# NodeNadelAdapter_v1_2.net
KiCad netlist of a schematic drawn in EAGLE
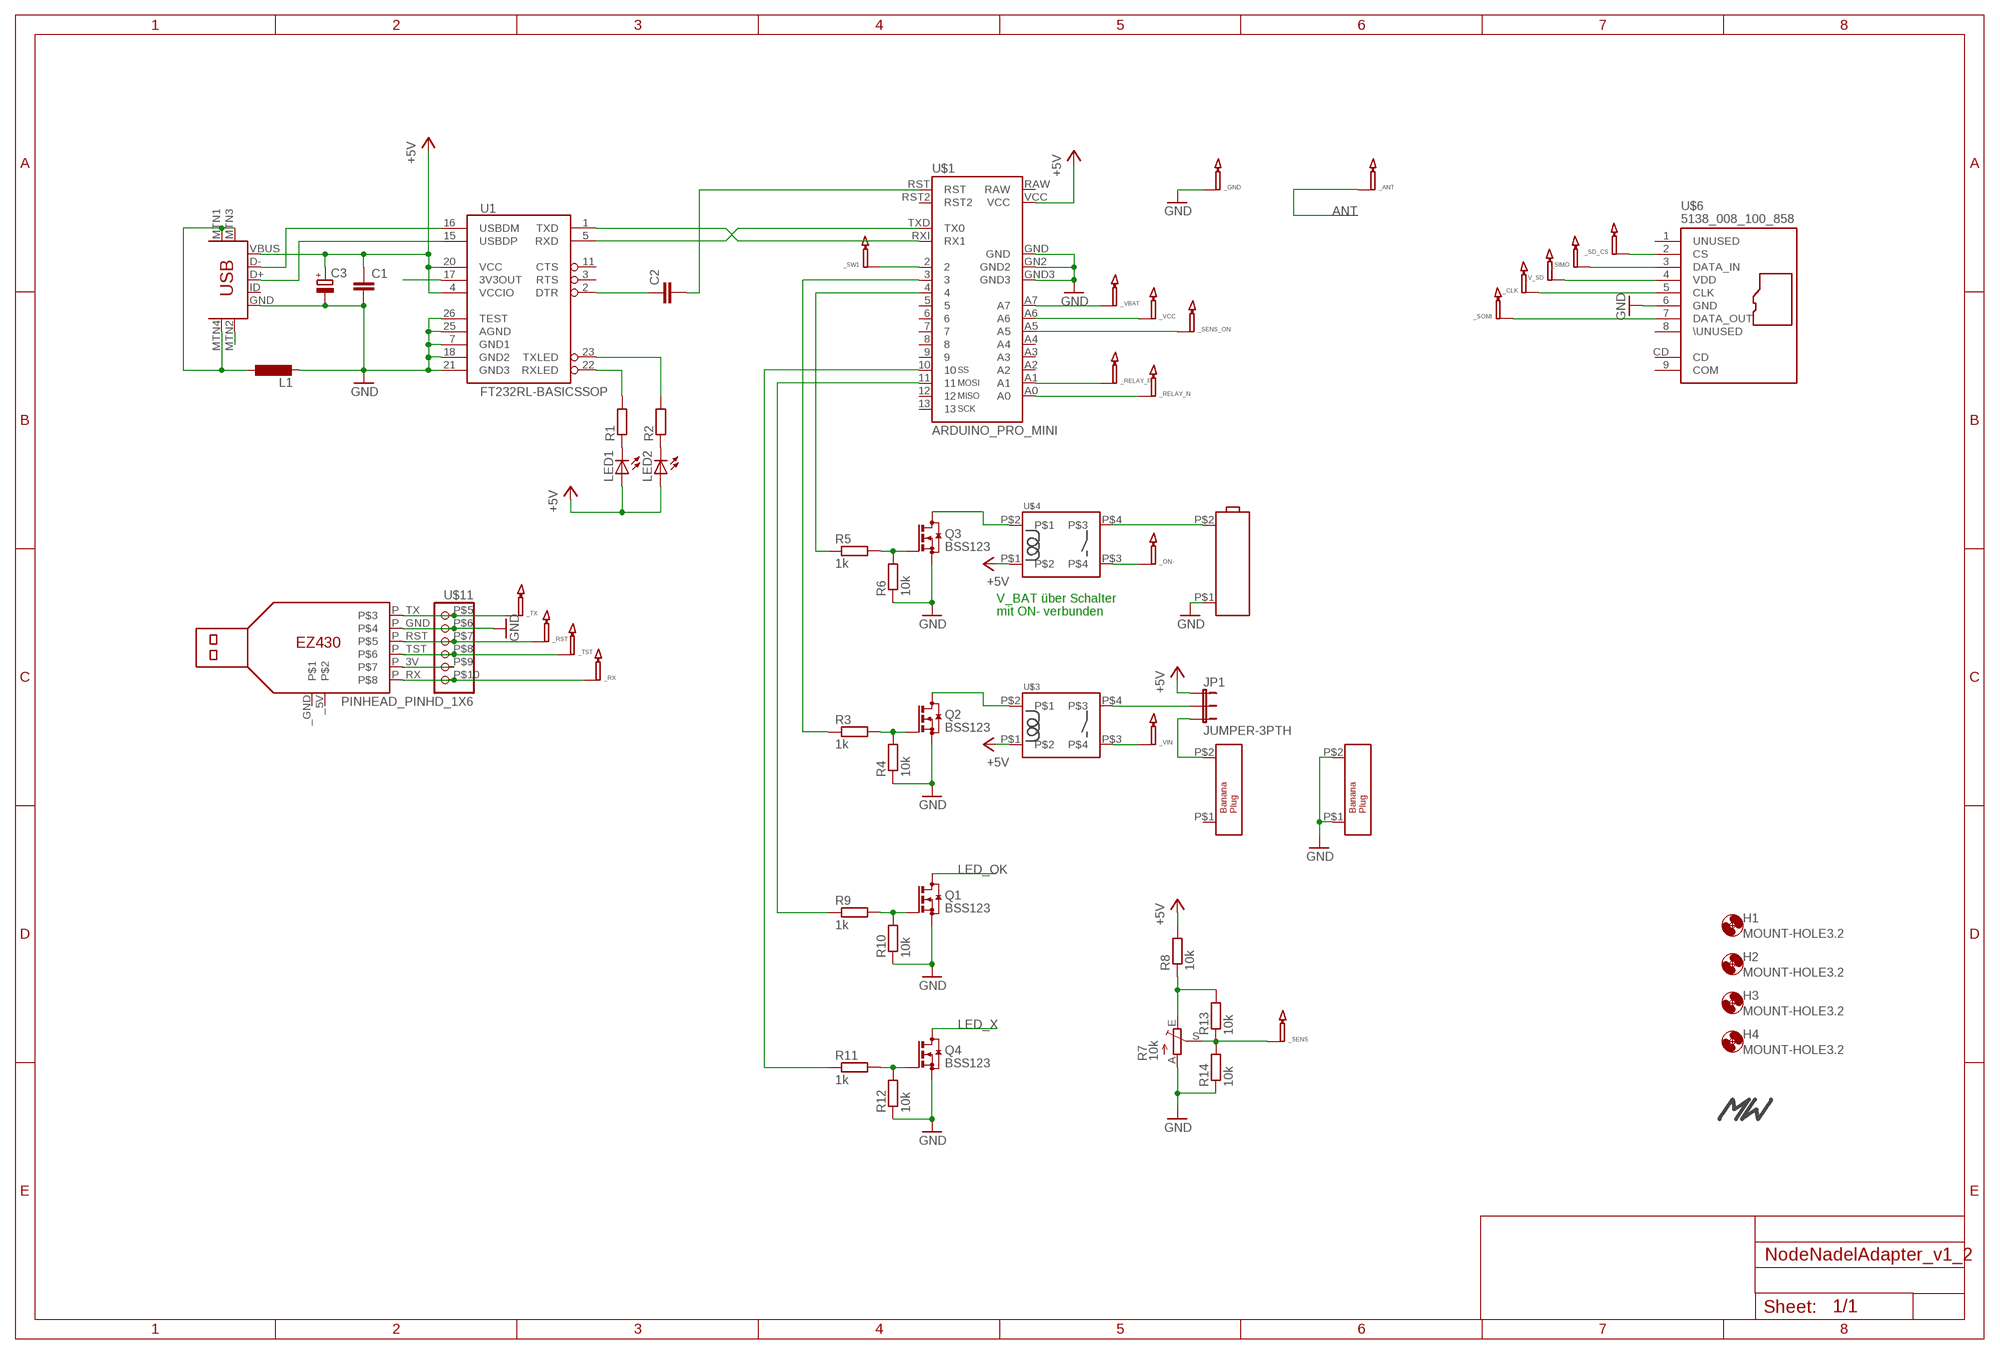
[diagram p0: schematic, sheet 1]

(export (version "E")
  (design (tool "Eeschema 10.0.6"))
  (components
    (comp (ref "C1")
      (value "C-EUC0603")
      (footprint "eagle-import:C0603")
      (libsource (lib "eagle-import") (part "C-EUC0603"))
    )
    (comp (ref "C2")
      (value "C-EUC0603")
      (footprint "eagle-import:C0603")
      (libsource (lib "eagle-import") (part "C-EUC0603"))
    )
    (comp (ref "C3")
      (value "CPOL-EUSMCA")
      (footprint "eagle-import:SMC_A")
      (libsource (lib "eagle-import") (part "CPOL-EUSMCA"))
    )
    (comp (ref "H1")
      (value "MOUNT-HOLE3.2")
      (footprint "eagle-import:3,2")
      (libsource (lib "eagle-import") (part "MOUNT-HOLE3.2"))
    )
    (comp (ref "H2")
      (value "MOUNT-HOLE3.2")
      (footprint "eagle-import:3,2")
      (libsource (lib "eagle-import") (part "MOUNT-HOLE3.2"))
    )
    (comp (ref "H3")
      (value "MOUNT-HOLE3.2")
      (footprint "eagle-import:3,2")
      (libsource (lib "eagle-import") (part "MOUNT-HOLE3.2"))
    )
    (comp (ref "H4")
      (value "MOUNT-HOLE3.2")
      (footprint "eagle-import:3,2")
      (libsource (lib "eagle-import") (part "MOUNT-HOLE3.2"))
    )
    (comp (ref "JP1")
      (value "JUMPER-3PTH")
      (footprint "eagle-import:1X03")
      (libsource (lib "eagle-import") (part "JUMPER-3PTH"))
    )
    (comp (ref "L1")
      (value "L-EUL2012C")
      (footprint "eagle-import:L2012C")
      (libsource (lib "eagle-import") (part "L-EUL2012C"))
    )
    (comp (ref "LED1")
      (value "LEDSML0805")
      (footprint "eagle-import:SML0805")
      (libsource (lib "eagle-import") (part "LEDSML0805"))
    )
    (comp (ref "LED2")
      (value "LEDSML0805")
      (footprint "eagle-import:SML0805")
      (libsource (lib "eagle-import") (part "LEDSML0805"))
    )
    (comp (ref "Q1")
      (value "BSS123")
      (footprint "eagle-import:SOT23")
      (libsource (lib "eagle-import") (part "BSS123"))
    )
    (comp (ref "Q2")
      (value "BSS123")
      (footprint "eagle-import:SOT23")
      (libsource (lib "eagle-import") (part "BSS123"))
    )
    (comp (ref "Q3")
      (value "BSS123")
      (footprint "eagle-import:SOT23")
      (libsource (lib "eagle-import") (part "BSS123"))
    )
    (comp (ref "Q4")
      (value "BSS123")
      (footprint "eagle-import:SOT23")
      (libsource (lib "eagle-import") (part "BSS123"))
    )
    (comp (ref "R1")
      (value "R-EU_R0603")
      (footprint "eagle-import:R0603")
      (libsource (lib "eagle-import") (part "R-EU_R0603"))
    )
    (comp (ref "R2")
      (value "R-EU_R0603")
      (footprint "eagle-import:R0603")
      (libsource (lib "eagle-import") (part "R-EU_R0603"))
    )
    (comp (ref "R3")
      (value "1k")
      (footprint "eagle-import:R0603")
      (libsource (lib "eagle-import") (part "R-EU_R0603"))
    )
    (comp (ref "R4")
      (value "10k")
      (footprint "eagle-import:R0603")
      (libsource (lib "eagle-import") (part "R-EU_R0603"))
    )
    (comp (ref "R5")
      (value "1k")
      (footprint "eagle-import:R0603")
      (libsource (lib "eagle-import") (part "R-EU_R0603"))
    )
    (comp (ref "R6")
      (value "10k")
      (footprint "eagle-import:R0603")
      (libsource (lib "eagle-import") (part "R-EU_R0603"))
    )
    (comp (ref "R7")
      (value "10k")
      (footprint "eagle-import:CA6V")
      (libsource (lib "eagle-import") (part "TRIM_EU-CA6V"))
    )
    (comp (ref "R8")
      (value "10k")
      (footprint "eagle-import:R0603")
      (libsource (lib "eagle-import") (part "R-EU_R0603"))
    )
    (comp (ref "R9")
      (value "1k")
      (footprint "eagle-import:R0603")
      (libsource (lib "eagle-import") (part "R-EU_R0603"))
    )
    (comp (ref "R10")
      (value "10k")
      (footprint "eagle-import:R0603")
      (libsource (lib "eagle-import") (part "R-EU_R0603"))
    )
    (comp (ref "R11")
      (value "1k")
      (footprint "eagle-import:R0603")
      (libsource (lib "eagle-import") (part "R-EU_R0603"))
    )
    (comp (ref "R12")
      (value "10k")
      (footprint "eagle-import:R0603")
      (libsource (lib "eagle-import") (part "R-EU_R0603"))
    )
    (comp (ref "R13")
      (value "10k")
      (footprint "eagle-import:R0603")
      (libsource (lib "eagle-import") (part "R-EU_R0603"))
    )
    (comp (ref "R14")
      (value "10k")
      (footprint "eagle-import:R0603")
      (libsource (lib "eagle-import") (part "R-EU_R0603"))
    )
    (comp (ref "U$1")
      (value "ARDUINO_PRO_MINI")
      (footprint "eagle-import:ARDUINO_PRO_MINI")
      (libsource (lib "eagle-import") (part "ARDUINO_PRO_MINI"))
    )
    (comp (ref "U$2")
      (value "BANANA_PLUG")
      (footprint "eagle-import:BANANA_PLUG")
      (libsource (lib "eagle-import") (part "BANANA_PLUG"))
    )
    (comp (ref "U$3")
      (value "RELAY_ZETTLER_AZ767")
      (footprint "eagle-import:RELAY_ZETTLER_AZ767")
      (libsource (lib "eagle-import") (part "RELAY_ZETTLER_AZ767"))
    )
    (comp (ref "U$4")
      (value "RELAY_ZETTLER_AZ767")
      (footprint "eagle-import:RELAY_ZETTLER_AZ767")
      (libsource (lib "eagle-import") (part "RELAY_ZETTLER_AZ767"))
    )
    (comp (ref "U$5")
      (value "EZ430")
      (footprint "eagle-import:EZ430")
      (libsource (lib "eagle-import") (part "EZ430"))
    )
    (comp (ref "U$6")
      (value "5138_008_100_858")
      (footprint "eagle-import:5138_008_100_858")
      (libsource (lib "eagle-import") (part "5138_008_100_858"))
    )
    (comp (ref "U$7")
      (value "USB-MINIB-5PIN")
      (footprint "eagle-import:USB-MINIB")
      (libsource (lib "eagle-import") (part "USB-MINIB-5PIN"))
    )
    (comp (ref "U$8")
      (value "AA_BATERIE_HALTER")
      (footprint "eagle-import:AA_BATERIE_HALTER")
      (libsource (lib "eagle-import") (part "AA_BATERIE_HALTER"))
    )
    (comp (ref "U$9")
      (value "BANANA_PLUG")
      (footprint "eagle-import:BANANA_PLUG")
      (libsource (lib "eagle-import") (part "BANANA_PLUG"))
    )
    (comp (ref "U$10")
      (value "MW_LOGO")
      (footprint "eagle-import:MW_11X5MM")
      (libsource (lib "eagle-import") (part "MW_LOGO"))
    )
    (comp (ref "U$11")
      (value "PINHEAD_PINHD_1X6")
      (footprint "eagle-import:PINHEAD_1X6S")
      (libsource (lib "eagle-import") (part "PINHEAD_PINHD_1X6"))
    )
    (comp (ref "U1")
      (value "FT232RL-BASICSSOP")
      (footprint "eagle-import:SSOP28DB")
      (libsource (lib "eagle-import") (part "FT232RL-BASICSSOP"))
    )
    (comp (ref "_ANT")
      (value "POGO_PINH")
      (footprint "eagle-import:POGO_PIN_V1.5")
      (libsource (lib "eagle-import") (part "POGO_PINH"))
    )
    (comp (ref "_CLK")
      (value "POGO_PINV")
      (footprint "eagle-import:POGO_PIN_V0.9")
      (libsource (lib "eagle-import") (part "POGO_PINV"))
    )
    (comp (ref "_GND")
      (value "POGO_PINV")
      (footprint "eagle-import:POGO_PIN_V0.9")
      (libsource (lib "eagle-import") (part "POGO_PINV"))
    )
    (comp (ref "_ON-")
      (value "POGO_PINH")
      (footprint "eagle-import:POGO_PIN_V1.5")
      (libsource (lib "eagle-import") (part "POGO_PINH"))
    )
    (comp (ref "_RELAY_N")
      (value "POGO_PINH")
      (footprint "eagle-import:POGO_PIN_V1.5")
      (libsource (lib "eagle-import") (part "POGO_PINH"))
    )
    (comp (ref "_RELAY_P")
      (value "POGO_PINH")
      (footprint "eagle-import:POGO_PIN_V1.5")
      (libsource (lib "eagle-import") (part "POGO_PINH"))
    )
    (comp (ref "_RST")
      (value "POGO_PINV")
      (footprint "eagle-import:POGO_PIN_V0.9")
      (libsource (lib "eagle-import") (part "POGO_PINV"))
    )
    (comp (ref "_RX")
      (value "POGO_PINV")
      (footprint "eagle-import:POGO_PIN_V0.9")
      (libsource (lib "eagle-import") (part "POGO_PINV"))
    )
    (comp (ref "_SD_CS")
      (value "POGO_PINV")
      (footprint "eagle-import:POGO_PIN_V0.9")
      (libsource (lib "eagle-import") (part "POGO_PINV"))
    )
    (comp (ref "_SENS")
      (value "POGO_PINH")
      (footprint "eagle-import:POGO_PIN_V1.5")
      (libsource (lib "eagle-import") (part "POGO_PINH"))
    )
    (comp (ref "_SENS_ON")
      (value "POGO_PINH")
      (footprint "eagle-import:POGO_PIN_V1.5")
      (libsource (lib "eagle-import") (part "POGO_PINH"))
    )
    (comp (ref "_SIMO")
      (value "POGO_PINV")
      (footprint "eagle-import:POGO_PIN_V0.9")
      (libsource (lib "eagle-import") (part "POGO_PINV"))
    )
    (comp (ref "_SOMI")
      (value "POGO_PINV")
      (footprint "eagle-import:POGO_PIN_V0.9")
      (libsource (lib "eagle-import") (part "POGO_PINV"))
    )
    (comp (ref "_SW1")
      (value "POGO_PINV")
      (footprint "eagle-import:POGO_PIN_V0.9")
      (libsource (lib "eagle-import") (part "POGO_PINV"))
    )
    (comp (ref "_TST")
      (value "POGO_PINV")
      (footprint "eagle-import:POGO_PIN_V0.9")
      (libsource (lib "eagle-import") (part "POGO_PINV"))
    )
    (comp (ref "_TX")
      (value "POGO_PINV")
      (footprint "eagle-import:POGO_PIN_V0.9")
      (libsource (lib "eagle-import") (part "POGO_PINV"))
    )
    (comp (ref "_VBAT")
      (value "POGO_PINH")
      (footprint "eagle-import:POGO_PIN_V1.5")
      (libsource (lib "eagle-import") (part "POGO_PINH"))
    )
    (comp (ref "_VCC")
      (value "POGO_PINH")
      (footprint "eagle-import:POGO_PIN_V1.5")
      (libsource (lib "eagle-import") (part "POGO_PINH"))
    )
    (comp (ref "_VIN")
      (value "POGO_PINH")
      (footprint "eagle-import:POGO_PIN_V1.5")
      (libsource (lib "eagle-import") (part "POGO_PINH"))
    )
    (comp (ref "_V_SD")
      (value "POGO_PINV")
      (footprint "eagle-import:POGO_PIN_V0.9")
      (libsource (lib "eagle-import") (part "POGO_PINV"))
    )
  )
  (nets
    (net (code "1") (name "+5V") (class "Default")
      (node (ref "C1") (pin "1") (pinfunction "1_1") (pintype "passive"))
      (node (ref "C3") (pin "+") (pinfunction "+_+") (pintype "passive"))
      (node (ref "JP1") (pin "1") (pinfunction "1_1") (pintype "passive"))
      (node (ref "LED1") (pin "A") (pinfunction "A_A") (pintype "passive"))
      (node (ref "LED2") (pin "A") (pinfunction "A_A") (pintype "passive"))
      (node (ref "R8") (pin "2") (pinfunction "2_2") (pintype "passive"))
      (node (ref "U$1") (pin "VCC") (pinfunction "VCC_VCC") (pintype "bidirectional"))
      (node (ref "U$3") (pin "P$1") (pinfunction "P$2_P$1") (pintype "bidirectional"))
      (node (ref "U$4") (pin "P$1") (pinfunction "P$2_P$1") (pintype "bidirectional"))
      (node (ref "U$7") (pin "VBUS") (pinfunction "VBUS_VBUS") (pintype "bidirectional"))
      (node (ref "U1") (pin "20") (pinfunction "VCC_20") (pintype "power_in"))
      (node (ref "U1") (pin "4") (pinfunction "VCCIO_4") (pintype "power_in"))
    )
    (net (code "2") (name "/ANT") (class "Default")
      (node (ref "_ANT") (pin "P$1") (pinfunction "P$1_P$1") (pintype "bidirectional"))
    )
    (net (code "3") (name "/LED_OK") (class "Default")
      (node (ref "Q1") (pin "3") (pinfunction "D_3") (pintype "passive"))
    )
    (net (code "4") (name "/LED_X") (class "Default")
      (node (ref "Q4") (pin "3") (pinfunction "D_3") (pintype "passive"))
    )
    (net (code "5") (name "GND") (class "Default")
      (node (ref "C1") (pin "2") (pinfunction "2_2") (pintype "passive"))
      (node (ref "C3") (pin "-") (pinfunction "-_-") (pintype "passive"))
      (node (ref "L1") (pin "2") (pinfunction "2_2") (pintype "passive"))
      (node (ref "Q1") (pin "2") (pinfunction "S_2") (pintype "passive"))
      (node (ref "Q2") (pin "2") (pinfunction "S_2") (pintype "passive"))
      (node (ref "Q3") (pin "2") (pinfunction "S_2") (pintype "passive"))
      (node (ref "Q4") (pin "2") (pinfunction "S_2") (pintype "passive"))
      (node (ref "R10") (pin "1") (pinfunction "1_1") (pintype "passive"))
      (node (ref "R12") (pin "1") (pinfunction "1_1") (pintype "passive"))
      (node (ref "R14") (pin "1") (pinfunction "1_1") (pintype "passive"))
      (node (ref "R4") (pin "1") (pinfunction "1_1") (pintype "passive"))
      (node (ref "R6") (pin "1") (pinfunction "1_1") (pintype "passive"))
      (node (ref "R7") (pin "A") (pinfunction "A_A") (pintype "passive"))
      (node (ref "U$1") (pin "GN2") (pinfunction "GND2_GN2") (pintype "bidirectional"))
      (node (ref "U$1") (pin "GND") (pinfunction "GND_GND") (pintype "bidirectional"))
      (node (ref "U$1") (pin "GND3") (pinfunction "GND3_GND3") (pintype "bidirectional"))
      (node (ref "U$11") (pin "P$6") (pinfunction "6_P$6") (pintype "passive"))
      (node (ref "U$5") (pin "P_GND") (pinfunction "P$4_P_GND") (pintype "bidirectional"))
      (node (ref "U$6") (pin "6") (pinfunction "GND_6") (pintype "bidirectional"))
      (node (ref "U$7") (pin "GND") (pinfunction "GND_GND") (pintype "bidirectional"))
      (node (ref "U$8") (pin "P$1") (pinfunction "P$1_P$1") (pintype "bidirectional"))
      (node (ref "U$9") (pin "P$1") (pinfunction "P$1_P$1") (pintype "bidirectional"))
      (node (ref "U$9") (pin "P$2") (pinfunction "P$2_P$2") (pintype "bidirectional"))
      (node (ref "U1") (pin "18") (pinfunction "GND2_18") (pintype "power_in"))
      (node (ref "U1") (pin "21") (pinfunction "GND3_21") (pintype "power_in"))
      (node (ref "U1") (pin "25") (pinfunction "AGND_25") (pintype "power_in"))
      (node (ref "U1") (pin "26") (pinfunction "TEST_26") (pintype "input"))
      (node (ref "U1") (pin "7") (pinfunction "GND1_7") (pintype "power_in"))
      (node (ref "_GND") (pin "P$1") (pinfunction "P$1_P$1") (pintype "bidirectional"))
    )
    (net (code "6") (name "Net-(C2-Pad2)") (class "Default")
      (node (ref "C2") (pin "2") (pinfunction "2_2") (pintype "passive"))
      (node (ref "U$1") (pin "RST") (pinfunction "RST_RST") (pintype "bidirectional"))
    )
    (net (code "7") (name "Net-(JP1-Pad3)") (class "Default")
      (node (ref "JP1") (pin "3") (pinfunction "3_3") (pintype "passive"))
      (node (ref "U$2") (pin "P$2") (pinfunction "P$2_P$2") (pintype "bidirectional"))
    )
    (net (code "8") (name "Net-(LED1-PadC)") (class "Default")
      (node (ref "LED1") (pin "C") (pinfunction "C_C") (pintype "passive"))
      (node (ref "R1") (pin "1") (pinfunction "1_1") (pintype "passive"))
    )
    (net (code "9") (name "Net-(LED2-PadC)") (class "Default")
      (node (ref "LED2") (pin "C") (pinfunction "C_C") (pintype "passive"))
      (node (ref "R2") (pin "1") (pinfunction "1_1") (pintype "passive"))
    )
    (net (code "10") (name "Net-(Q1-G)") (class "Default")
      (node (ref "Q1") (pin "1") (pinfunction "G_1") (pintype "passive"))
      (node (ref "R10") (pin "2") (pinfunction "2_2") (pintype "passive"))
      (node (ref "R9") (pin "2") (pinfunction "2_2") (pintype "passive"))
    )
    (net (code "11") (name "Net-(Q2-D)") (class "Default")
      (node (ref "Q2") (pin "3") (pinfunction "D_3") (pintype "passive"))
      (node (ref "U$3") (pin "P$2") (pinfunction "P$1_P$2") (pintype "bidirectional"))
    )
    (net (code "12") (name "Net-(Q2-G)") (class "Default")
      (node (ref "Q2") (pin "1") (pinfunction "G_1") (pintype "passive"))
      (node (ref "R3") (pin "2") (pinfunction "2_2") (pintype "passive"))
      (node (ref "R4") (pin "2") (pinfunction "2_2") (pintype "passive"))
    )
    (net (code "13") (name "Net-(Q3-D)") (class "Default")
      (node (ref "Q3") (pin "3") (pinfunction "D_3") (pintype "passive"))
      (node (ref "U$4") (pin "P$2") (pinfunction "P$1_P$2") (pintype "bidirectional"))
    )
    (net (code "14") (name "Net-(Q3-G)") (class "Default")
      (node (ref "Q3") (pin "1") (pinfunction "G_1") (pintype "passive"))
      (node (ref "R5") (pin "2") (pinfunction "2_2") (pintype "passive"))
      (node (ref "R6") (pin "2") (pinfunction "2_2") (pintype "passive"))
    )
    (net (code "15") (name "Net-(Q4-G)") (class "Default")
      (node (ref "Q4") (pin "1") (pinfunction "G_1") (pintype "passive"))
      (node (ref "R11") (pin "2") (pinfunction "2_2") (pintype "passive"))
      (node (ref "R12") (pin "2") (pinfunction "2_2") (pintype "passive"))
    )
    (net (code "16") (name "Net-(R3-Pad1)") (class "Default")
      (node (ref "R3") (pin "1") (pinfunction "1_1") (pintype "passive"))
      (node (ref "U$1") (pin "3") (pinfunction "3_3") (pintype "bidirectional"))
    )
    (net (code "17") (name "Net-(R5-Pad1)") (class "Default")
      (node (ref "R5") (pin "1") (pinfunction "1_1") (pintype "passive"))
      (node (ref "U$1") (pin "4") (pinfunction "4_4") (pintype "bidirectional"))
    )
    (net (code "18") (name "Net-(R9-Pad1)") (class "Default")
      (node (ref "R9") (pin "1") (pinfunction "1_1") (pintype "passive"))
      (node (ref "U$1") (pin "11") (pinfunction "11_11") (pintype "bidirectional"))
    )
    (net (code "19") (name "Net-(R11-Pad1)") (class "Default")
      (node (ref "R11") (pin "1") (pinfunction "1_1") (pintype "passive"))
      (node (ref "U$1") (pin "10") (pinfunction "10_10") (pintype "bidirectional"))
    )
    (net (code "20") (name "Net-(R13-Pad1)") (class "Default")
      (node (ref "R13") (pin "1") (pinfunction "1_1") (pintype "passive"))
      (node (ref "R14") (pin "2") (pinfunction "2_2") (pintype "passive"))
      (node (ref "R7") (pin "S") (pinfunction "S_S") (pintype "passive"))
      (node (ref "_SENS") (pin "P$1") (pinfunction "P$1_P$1") (pintype "bidirectional"))
    )
    (net (code "21") (name "Net-(R13-Pad2)") (class "Default")
      (node (ref "R13") (pin "2") (pinfunction "2_2") (pintype "passive"))
      (node (ref "R7") (pin "E") (pinfunction "E_E") (pintype "passive"))
      (node (ref "R8") (pin "1") (pinfunction "1_1") (pintype "passive"))
    )
    (net (code "22") (name "Net-(U$1-Pad2)") (class "Default")
      (node (ref "U$1") (pin "2") (pinfunction "2_2") (pintype "bidirectional"))
      (node (ref "_SW1") (pin "P$1") (pinfunction "P$1_P$1") (pintype "bidirectional"))
    )
    (net (code "23") (name "Net-(U$1-PadA0)") (class "Default")
      (node (ref "U$1") (pin "A0") (pinfunction "A0_A0") (pintype "bidirectional"))
      (node (ref "_RELAY_N") (pin "P$1") (pinfunction "P$1_P$1") (pintype "bidirectional"))
    )
    (net (code "24") (name "Net-(U$1-PadA1)") (class "Default")
      (node (ref "U$1") (pin "A1") (pinfunction "A1_A1") (pintype "bidirectional"))
      (node (ref "_RELAY_P") (pin "P$1") (pinfunction "P$1_P$1") (pintype "bidirectional"))
    )
    (net (code "25") (name "Net-(U$1-PadA5)") (class "Default")
      (node (ref "U$1") (pin "A5") (pinfunction "A5_A5") (pintype "bidirectional"))
      (node (ref "_SENS_ON") (pin "P$1") (pinfunction "P$1_P$1") (pintype "bidirectional"))
    )
    (net (code "26") (name "Net-(U$1-PadA6)") (class "Default")
      (node (ref "U$1") (pin "A6") (pinfunction "A6_A6") (pintype "bidirectional"))
      (node (ref "_VCC") (pin "P$1") (pinfunction "P$1_P$1") (pintype "bidirectional"))
    )
    (net (code "27") (name "Net-(U$1-PadA7)") (class "Default")
      (node (ref "U$1") (pin "A7") (pinfunction "A7_A7") (pintype "bidirectional"))
      (node (ref "_VBAT") (pin "P$1") (pinfunction "P$1_P$1") (pintype "bidirectional"))
    )
    (net (code "28") (name "Net-(U$1-RX1)") (class "Default")
      (node (ref "U$1") (pin "RXI") (pinfunction "RX1_RXI") (pintype "bidirectional"))
      (node (ref "U1") (pin "1") (pinfunction "TXD_1") (pintype "output"))
    )
    (net (code "29") (name "Net-(U$1-TX0)") (class "Default")
      (node (ref "U$1") (pin "TXD") (pinfunction "TX0_TXD") (pintype "bidirectional"))
      (node (ref "U1") (pin "5") (pinfunction "RXD_5") (pintype "input"))
    )
    (net (code "30") (name "Net-(U$3-P$3)") (class "Default")
      (node (ref "JP1") (pin "2") (pinfunction "2_2") (pintype "passive"))
      (node (ref "U$3") (pin "P$4") (pinfunction "P$3_P$4") (pintype "bidirectional"))
    )
    (net (code "31") (name "Net-(U$3-P$4)") (class "Default")
      (node (ref "U$3") (pin "P$3") (pinfunction "P$4_P$3") (pintype "bidirectional"))
      (node (ref "_VIN") (pin "P$1") (pinfunction "P$1_P$1") (pintype "bidirectional"))
    )
    (net (code "32") (name "Net-(U$4-P$3)") (class "Default")
      (node (ref "U$4") (pin "P$4") (pinfunction "P$3_P$4") (pintype "bidirectional"))
      (node (ref "U$8") (pin "P$2") (pinfunction "P$2_P$2") (pintype "bidirectional"))
    )
    (net (code "33") (name "Net-(U$4-P$4)") (class "Default")
      (node (ref "U$4") (pin "P$3") (pinfunction "P$4_P$3") (pintype "bidirectional"))
      (node (ref "_ON-") (pin "P$1") (pinfunction "P$1_P$1") (pintype "bidirectional"))
    )
    (net (code "34") (name "Net-(U$6-CLK)") (class "Default")
      (node (ref "U$6") (pin "5") (pinfunction "CLK_5") (pintype "bidirectional"))
      (node (ref "_CLK") (pin "P$1") (pinfunction "P$1_P$1") (pintype "bidirectional"))
    )
    (net (code "35") (name "Net-(U$6-CS)") (class "Default")
      (node (ref "U$6") (pin "2") (pinfunction "CS_2") (pintype "bidirectional"))
      (node (ref "_SD_CS") (pin "P$1") (pinfunction "P$1_P$1") (pintype "bidirectional"))
    )
    (net (code "36") (name "Net-(U$6-DATA_IN)") (class "Default")
      (node (ref "U$6") (pin "3") (pinfunction "DATA_IN_3") (pintype "bidirectional"))
      (node (ref "_SIMO") (pin "P$1") (pinfunction "P$1_P$1") (pintype "bidirectional"))
    )
    (net (code "37") (name "Net-(U$6-DATA_OUT)") (class "Default")
      (node (ref "U$6") (pin "7") (pinfunction "DATA_OUT_7") (pintype "bidirectional"))
      (node (ref "_SOMI") (pin "P$1") (pinfunction "P$1_P$1") (pintype "bidirectional"))
    )
    (net (code "38") (name "Net-(U$6-VDD)") (class "Default")
      (node (ref "U$6") (pin "4") (pinfunction "VDD_4") (pintype "bidirectional"))
      (node (ref "_V_SD") (pin "P$1") (pinfunction "P$1_P$1") (pintype "bidirectional"))
    )
    (net (code "39") (name "Net-(U$7-MTN1)") (class "Default")
      (node (ref "L1") (pin "1") (pinfunction "1_1") (pintype "passive"))
      (node (ref "U$7") (pin "MTN1") (pinfunction "MTN2_MTN1") (pintype "bidirectional"))
      (node (ref "U$7") (pin "MTN3") (pinfunction "MTN1_MTN3") (pintype "bidirectional"))
      (node (ref "U$7") (pin "MTN4") (pinfunction "MTN4_MTN4") (pintype "bidirectional"))
    )
    (net (code "40") (name "Net-(U$11-5)") (class "Default")
      (node (ref "U$11") (pin "P$5") (pinfunction "5_P$5") (pintype "passive"))
      (node (ref "U$5") (pin "P_TX") (pinfunction "P$3_P_TX") (pintype "bidirectional"))
      (node (ref "_TX") (pin "P$1") (pinfunction "P$1_P$1") (pintype "bidirectional"))
    )
    (net (code "41") (name "Net-(U$11-7)") (class "Default")
      (node (ref "U$11") (pin "P$7") (pinfunction "7_P$7") (pintype "passive"))
      (node (ref "U$5") (pin "P_RST") (pinfunction "P$5_P_RST") (pintype "bidirectional"))
      (node (ref "_RST") (pin "P$1") (pinfunction "P$1_P$1") (pintype "bidirectional"))
    )
    (net (code "42") (name "Net-(U$11-8)") (class "Default")
      (node (ref "U$11") (pin "P$8") (pinfunction "8_P$8") (pintype "passive"))
      (node (ref "U$5") (pin "P_TST") (pinfunction "P$6_P_TST") (pintype "bidirectional"))
      (node (ref "_TST") (pin "P$1") (pinfunction "P$1_P$1") (pintype "bidirectional"))
    )
    (net (code "43") (name "Net-(U$11-9)") (class "Default")
      (node (ref "U$11") (pin "P$9") (pinfunction "9_P$9") (pintype "passive"))
      (node (ref "U$5") (pin "P_3V") (pinfunction "P$7_P_3V") (pintype "bidirectional"))
    )
    (net (code "44") (name "Net-(U$11-10)") (class "Default")
      (node (ref "U$11") (pin "P$10") (pinfunction "10_P$10") (pintype "passive"))
      (node (ref "U$5") (pin "P_RX") (pinfunction "P$8_P_RX") (pintype "bidirectional"))
      (node (ref "_RX") (pin "P$1") (pinfunction "P$1_P$1") (pintype "bidirectional"))
    )
    (net (code "45") (name "Net-(U1-DTR)") (class "Default")
      (node (ref "C2") (pin "1") (pinfunction "1_1") (pintype "passive"))
      (node (ref "U1") (pin "2") (pinfunction "DTR_2") (pintype "bidirectional"))
    )
    (net (code "46") (name "Net-(U1-RXLED)") (class "Default")
      (node (ref "R1") (pin "2") (pinfunction "2_2") (pintype "passive"))
      (node (ref "U1") (pin "22") (pinfunction "RXLED_22") (pintype "bidirectional"))
    )
    (net (code "47") (name "Net-(U1-TXLED)") (class "Default")
      (node (ref "R2") (pin "2") (pinfunction "2_2") (pintype "passive"))
      (node (ref "U1") (pin "23") (pinfunction "TXLED_23") (pintype "bidirectional"))
    )
    (net (code "48") (name "Net-(U1-USBDM)") (class "Default")
      (node (ref "U$7") (pin "D-") (pinfunction "D-_D-") (pintype "bidirectional"))
      (node (ref "U1") (pin "16") (pinfunction "USBDM_16") (pintype "bidirectional"))
    )
    (net (code "49") (name "Net-(U1-USBDP)") (class "Default")
      (node (ref "U$7") (pin "D+") (pinfunction "D+_D+") (pintype "bidirectional"))
      (node (ref "U1") (pin "15") (pinfunction "USBDP_15") (pintype "bidirectional"))
    )
    (net (code "50") (name "unconnected-(U$1-Pad5)") (class "Default")
      (node (ref "U$1") (pin "5") (pinfunction "5_5") (pintype "bidirectional"))
    )
    (net (code "51") (name "unconnected-(U$1-Pad6)") (class "Default")
      (node (ref "U$1") (pin "6") (pinfunction "6_6") (pintype "bidirectional"))
    )
    (net (code "52") (name "unconnected-(U$1-Pad7)") (class "Default")
      (node (ref "U$1") (pin "7") (pinfunction "7_7") (pintype "bidirectional"))
    )
    (net (code "53") (name "unconnected-(U$1-Pad8)") (class "Default")
      (node (ref "U$1") (pin "8") (pinfunction "8_8") (pintype "bidirectional"))
    )
    (net (code "54") (name "unconnected-(U$1-Pad9)") (class "Default")
      (node (ref "U$1") (pin "9") (pinfunction "9_9") (pintype "bidirectional"))
    )
    (net (code "55") (name "unconnected-(U$1-Pad12)") (class "Default")
      (node (ref "U$1") (pin "12") (pinfunction "12_12") (pintype "bidirectional"))
    )
    (net (code "56") (name "unconnected-(U$1-Pad13)") (class "Default")
      (node (ref "U$1") (pin "13") (pinfunction "13_13") (pintype "bidirectional"))
    )
    (net (code "57") (name "unconnected-(U$1-PadA2)") (class "Default")
      (node (ref "U$1") (pin "A2") (pinfunction "A2_A2") (pintype "bidirectional"))
    )
    (net (code "58") (name "unconnected-(U$1-PadA3)") (class "Default")
      (node (ref "U$1") (pin "A3") (pinfunction "A3_A3") (pintype "bidirectional"))
    )
    (net (code "59") (name "unconnected-(U$1-PadA4)") (class "Default")
      (node (ref "U$1") (pin "A4") (pinfunction "A4_A4") (pintype "bidirectional"))
    )
    (net (code "60") (name "unconnected-(U$1-PadRAW)") (class "Default")
      (node (ref "U$1") (pin "RAW") (pinfunction "RAW_RAW") (pintype "bidirectional"))
    )
    (net (code "61") (name "unconnected-(U$1-PadRST2)") (class "Default")
      (node (ref "U$1") (pin "RST2") (pinfunction "RST2_RST2") (pintype "bidirectional"))
    )
    (net (code "62") (name "unconnected-(U$2-PadP$1)") (class "Default")
      (node (ref "U$2") (pin "P$1") (pinfunction "P$1_P$1") (pintype "bidirectional"))
    )
    (net (code "63") (name "unconnected-(U$5-P$1-Pad_GND)") (class "Default")
      (node (ref "U$5") (pin "_GND") (pinfunction "P$1__GND") (pintype "bidirectional"))
    )
    (net (code "64") (name "unconnected-(U$5-P$2-Pad_5V)") (class "Default")
      (node (ref "U$5") (pin "_5V") (pinfunction "P$2__5V") (pintype "bidirectional"))
    )
    (net (code "65") (name "unconnected-(U$6-COM-Pad9)") (class "Default")
      (node (ref "U$6") (pin "9") (pinfunction "COM_9") (pintype "bidirectional"))
    )
    (net (code "66") (name "unconnected-(U$6-PadCD)") (class "Default")
      (node (ref "U$6") (pin "CD") (pinfunction "CD_CD") (pintype "bidirectional"))
    )
    (net (code "67") (name "unconnected-(U$6-UNUSED-Pad1)") (class "Default")
      (node (ref "U$6") (pin "1") (pinfunction "UNUSED_1") (pintype "bidirectional"))
    )
    (net (code "68") (name "unconnected-(U$6-\\UNUSED-Pad8)") (class "Default")
      (node (ref "U$6") (pin "8") (pinfunction "\\UNUSED_8") (pintype "bidirectional"))
    )
    (net (code "69") (name "unconnected-(U$7-MTN3-PadMTN2)") (class "Default")
      (node (ref "U$7") (pin "MTN2") (pinfunction "MTN3_MTN2") (pintype "bidirectional"))
    )
    (net (code "70") (name "unconnected-(U$7-PadID)") (class "Default")
      (node (ref "U$7") (pin "ID") (pinfunction "ID_ID") (pintype "bidirectional"))
    )
    (net (code "71") (name "unconnected-(U1-3V3OUT-Pad17)") (class "Default")
      (node (ref "U1") (pin "17") (pinfunction "3V3OUT_17") (pintype "output"))
    )
    (net (code "72") (name "unconnected-(U1-CTS-Pad11)") (class "Default")
      (node (ref "U1") (pin "11") (pinfunction "CTS_11") (pintype "bidirectional"))
    )
    (net (code "73") (name "unconnected-(U1-RTS-Pad3)") (class "Default")
      (node (ref "U1") (pin "3") (pinfunction "RTS_3") (pintype "bidirectional"))
    )
  )
)
